# ADJ_LDO.net
KiCad netlist of a schematic drawn in Altium Designer
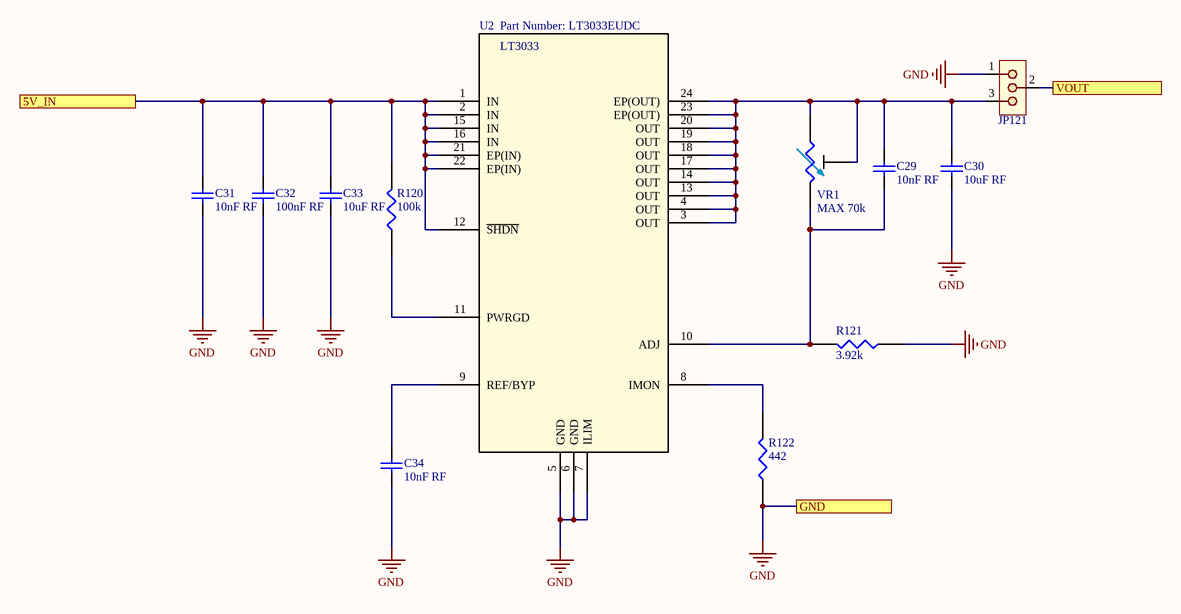
[diagram p0: ADJ_LDO.SchDoc]

(export (version "E")
  (design (tool "Eeschema 10.0.6"))
  (components
    (comp (ref "C29")
      (value "10nF RF")
      (footprint "CLS_Library:C0805")
      (description "CAP 10nF 50V RF")
      (fields
        (field (name "MANUFACTURER") "Taiyo Yuden")
        (field (name "MANUFACTURER PART NUMBER") "UMK212SD103KD-T")
      )
      (libsource (lib "CLS_Library") (part "UMK212SD103KD-T"))
    )
    (comp (ref "C30")
      (value "10uF RF")
      (footprint "CLS_Library:C0805")
      (description "CAP 10nF 50V RF")
      (fields
        (field (name "MANUFACTURER") "Taiyo Yuden")
        (field (name "MANUFACTURER PART NUMBER") "UMK212SD103KD-T")
      )
      (libsource (lib "CLS_Library") (part "UMK212SD103KD-T"))
    )
    (comp (ref "C31")
      (value "10nF RF")
      (footprint "C0805")
      (description "CAP 10nF 50V RF")
      (fields
        (field (name "MANUFACTURER") "Taiyo Yuden")
        (field (name "MANUFACTURER PART NUMBER") "UMK212SD103KD-T")
      )
      (libsource (lib "CLS_Library") (part "UMK212SD103KD-T"))
    )
    (comp (ref "C32")
      (value "100nF RF")
      (footprint "C0805")
      (description "CAP 10nF 50V RF")
      (fields
        (field (name "MANUFACTURER") "Taiyo Yuden")
        (field (name "MANUFACTURER PART NUMBER") "UMK212SD103KD-T")
      )
      (libsource (lib "CLS_Library") (part "UMK212SD103KD-T"))
    )
    (comp (ref "C33")
      (value "10uF RF")
      (footprint "C0805")
      (description "CAP 10nF 50V RF")
      (fields
        (field (name "MANUFACTURER") "Taiyo Yuden")
        (field (name "MANUFACTURER PART NUMBER") "UMK212SD103KD-T")
      )
      (libsource (lib "CLS_Library") (part "UMK212SD103KD-T"))
    )
    (comp (ref "C34")
      (value "10nF RF")
      (footprint "C0805")
      (description "CAP 10nF 50V RF")
      (fields
        (field (name "MANUFACTURER") "Taiyo Yuden")
        (field (name "MANUFACTURER PART NUMBER") "UMK212SD103KD-T")
      )
      (libsource (lib "CLS_Library") (part "UMK212SD103KD-T"))
    )
    (comp (ref "JP121")
      (value "Jumper")
      (footprint "01x03_0.1in_th_straight_b_nom")
      (description "01X03 generic terminal connector")
      (libsource (lib "CLS_Library") (part "Jumper-01x03"))
    )
    (comp (ref "R120") (value "100k") (footprint "R0805") (libsource (lib "CLS_Library") (part "RES")))
    (comp (ref "R121") (value "3.92k") (footprint "R0805") (libsource (lib "CLS_Library") (part "RES")))
    (comp (ref "R122") (value "442") (footprint "R0805") (libsource (lib "CLS_Library") (part "RES")))
    (comp (ref "U2")
      (value "Part Number: LT3033EUDC")
      (footprint "LT3033")
      (description "No Description Available")
      (fields
        (field (name "MANUFACTURER_PART_NUMBER") "LT3033EUDC")
        (field (name "COPYRIGHT") "Copyright (C) 2018 Accelerated Designs. All rights reserved")
      )
      (libsource (lib "CLS_Library") (part "LT3033EUDC"))
    )
    (comp (ref "VR1")
      (value "MAX 70k")
      (footprint "res_var_5turn")
      (libsource (lib "CLS_Library") (part "Var_RES"))
    )
  )
  (nets
    (net (code "1") (name "/5V_IN") (class "Default")
      (node (ref "C31") (pin "2") (pinfunction "2_2") (pintype "passive"))
      (node (ref "C32") (pin "2") (pinfunction "2_2") (pintype "passive"))
      (node (ref "C33") (pin "2") (pinfunction "2_2") (pintype "passive"))
      (node (ref "R120") (pin "2") (pinfunction "2_2") (pintype "passive"))
      (node (ref "U2") (pin "1") (pinfunction "IN_1") (pintype "passive"))
      (node (ref "U2") (pin "12") (pinfunction "~{SHDN}_12") (pintype "passive"))
      (node (ref "U2") (pin "15") (pinfunction "IN_15") (pintype "passive"))
      (node (ref "U2") (pin "16") (pinfunction "IN_16") (pintype "passive"))
      (node (ref "U2") (pin "2") (pinfunction "IN_2") (pintype "passive"))
      (node (ref "U2") (pin "21") (pinfunction "EP(IN)_21") (pintype "passive"))
      (node (ref "U2") (pin "22") (pinfunction "EP(IN)_22") (pintype "passive"))
    )
    (net (code "2") (name "/VOUT") (class "Default")
      (node (ref "JP121") (pin "2") (pinfunction "2_2") (pintype "passive"))
    )
    (net (code "3") (name "GND") (class "Default")
      (node (ref "C30") (pin "1") (pinfunction "1_1") (pintype "passive"))
      (node (ref "C31") (pin "1") (pinfunction "1_1") (pintype "passive"))
      (node (ref "C32") (pin "1") (pinfunction "1_1") (pintype "passive"))
      (node (ref "C33") (pin "1") (pinfunction "1_1") (pintype "passive"))
      (node (ref "C34") (pin "1") (pinfunction "1_1") (pintype "passive"))
      (node (ref "JP121") (pin "1") (pinfunction "1_1") (pintype "passive"))
      (node (ref "R121") (pin "1") (pinfunction "1_1") (pintype "passive"))
      (node (ref "R122") (pin "1") (pinfunction "1_1") (pintype "passive"))
      (node (ref "U2") (pin "5") (pinfunction "GND_5") (pintype "passive"))
      (node (ref "U2") (pin "6") (pinfunction "GND_6") (pintype "passive"))
      (node (ref "U2") (pin "7") (pinfunction "ILIM_7") (pintype "passive"))
    )
    (net (code "4") (name "Net-(C29-Pad2)") (class "Default")
      (node (ref "C29") (pin "2") (pinfunction "2_2") (pintype "passive"))
      (node (ref "C30") (pin "2") (pinfunction "2_2") (pintype "passive"))
      (node (ref "JP121") (pin "3") (pinfunction "3_3") (pintype "passive"))
      (node (ref "U2") (pin "13") (pinfunction "OUT_13") (pintype "passive"))
      (node (ref "U2") (pin "14") (pinfunction "OUT_14") (pintype "passive"))
      (node (ref "U2") (pin "17") (pinfunction "OUT_17") (pintype "passive"))
      (node (ref "U2") (pin "18") (pinfunction "OUT_18") (pintype "passive"))
      (node (ref "U2") (pin "19") (pinfunction "OUT_19") (pintype "passive"))
      (node (ref "U2") (pin "20") (pinfunction "OUT_20") (pintype "passive"))
      (node (ref "U2") (pin "23") (pinfunction "EP(OUT)_23") (pintype "passive"))
      (node (ref "U2") (pin "24") (pinfunction "EP(OUT)_24") (pintype "passive"))
      (node (ref "U2") (pin "3") (pinfunction "OUT_3") (pintype "passive"))
      (node (ref "U2") (pin "4") (pinfunction "OUT_4") (pintype "passive"))
      (node (ref "VR1") (pin "1") (pinfunction "1_1") (pintype "passive"))
      (node (ref "VR1") (pin "2") (pinfunction "2_2") (pintype "passive"))
    )
    (net (code "5") (name "Net-(U2-ADJ)") (class "Default")
      (node (ref "C29") (pin "1") (pinfunction "1_1") (pintype "passive"))
      (node (ref "R121") (pin "2") (pinfunction "2_2") (pintype "passive"))
      (node (ref "U2") (pin "10") (pinfunction "ADJ_10") (pintype "passive"))
      (node (ref "VR1") (pin "3") (pinfunction "3_3") (pintype "passive"))
    )
    (net (code "6") (name "Net-(U2-IMON)") (class "Default")
      (node (ref "R122") (pin "2") (pinfunction "2_2") (pintype "passive"))
      (node (ref "U2") (pin "8") (pinfunction "IMON_8") (pintype "passive"))
    )
    (net (code "7") (name "Net-(U2-PWRGD)") (class "Default")
      (node (ref "R120") (pin "1") (pinfunction "1_1") (pintype "passive"))
      (node (ref "U2") (pin "11") (pinfunction "PWRGD_11") (pintype "passive"))
    )
    (net (code "8") (name "Net-(U2-REF{slash}BYP)") (class "Default")
      (node (ref "C34") (pin "2") (pinfunction "2_2") (pintype "passive"))
      (node (ref "U2") (pin "9") (pinfunction "REF/BYP_9") (pintype "passive"))
    )
  )
)
